# AD_DA.net
KiCad netlist of a schematic drawn in Altium Designer
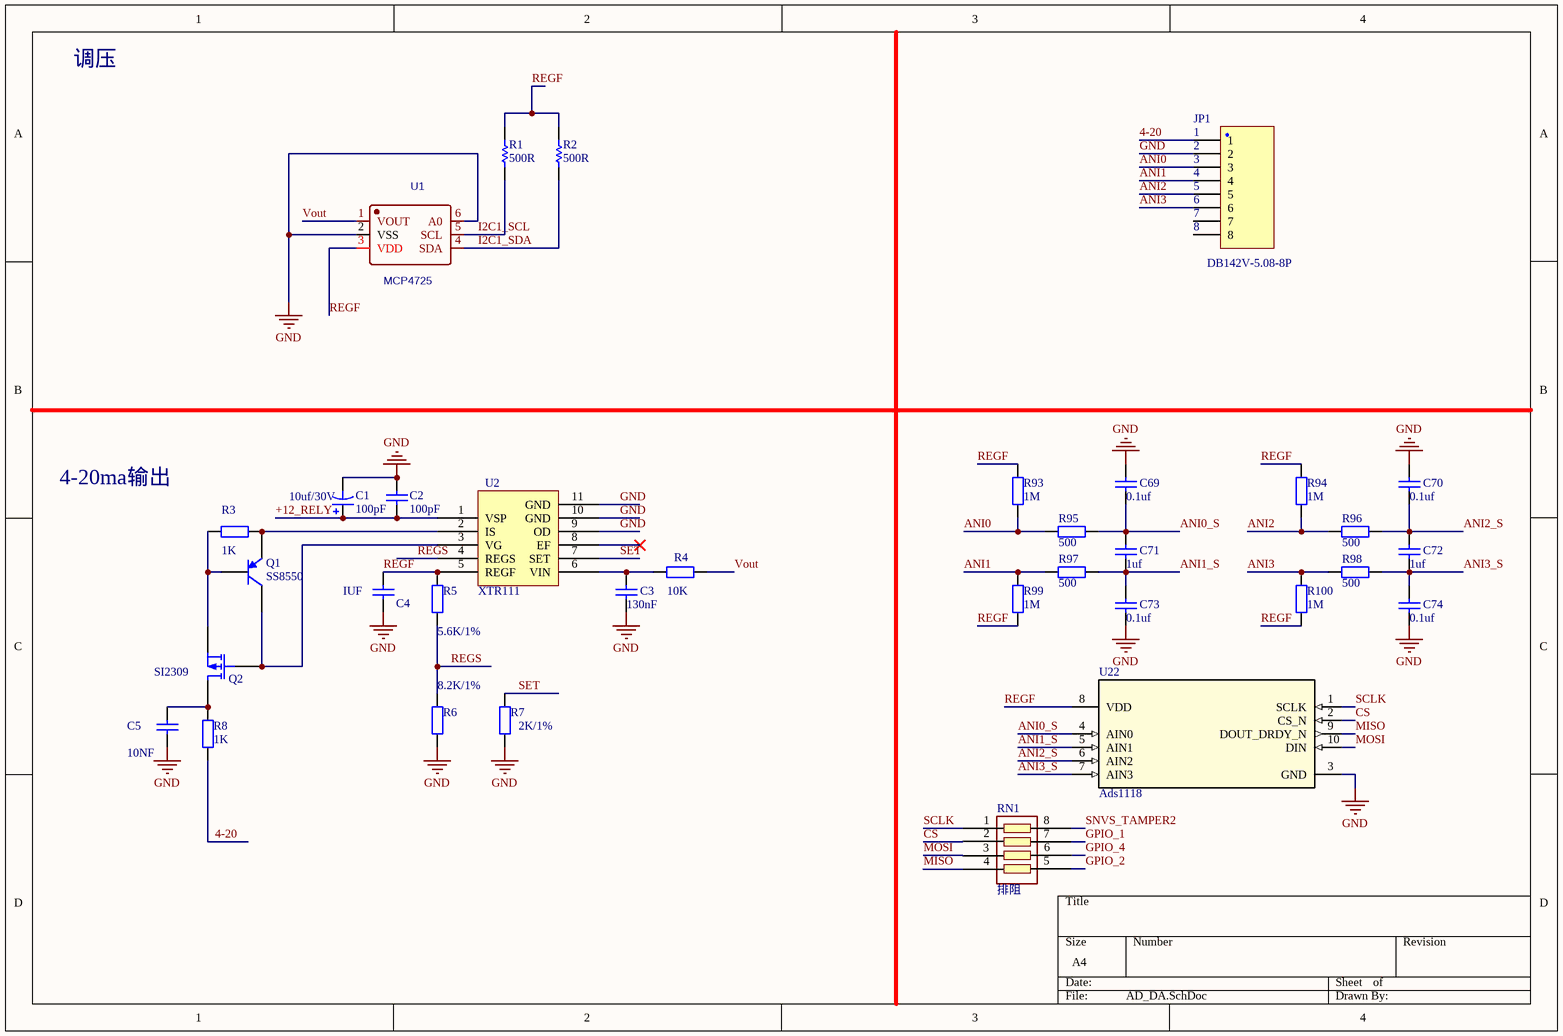
[diagram p0: AD_DA.SchDoc]

(export (version "E")
  (design (tool "Eeschema 10.0.6"))
  (components
    (comp (ref "C1")
      (value "10uf/30V")
      (footprint "CC5.05.4")
      (description "Polarized Capacitor (Radial)")
      (fields (field (name "ALTIUM_VALUE") "100pF") (field (name "PUBLISHER") "Altium Limited"))
      (libsource (lib "Miscellaneous Devices") (part "Cap Pol1"))
    )
    (comp (ref "C2")
      (value "100pF")
      (footprint "0603c")
      (description "Capacitor")
      (fields (field (name "Comment") "104") (field (name "PUBLISHER") "Altium Limited"))
      (libsource (lib "Miscellaneous Devices") (part "Cap"))
    )
    (comp (ref "C3")
      (value "130nF")
      (footprint "0603")
      (description "Capacitor")
      (libsource (lib "MyStandardSchLib") (part "Cap Smd"))
    )
    (comp (ref "C4")
      (value "IUF")
      (footprint "0603c")
      (description "Capacitor")
      (fields (field (name "PUBLISHER") "Altium Limited"))
      (libsource (lib "Miscellaneous Devices") (part "Cap"))
    )
    (comp (ref "C5")
      (value "10NF")
      (footprint "0603c")
      (description "Capacitor")
      (fields (field (name "PUBLISHER") "Altium Limited"))
      (libsource (lib "Miscellaneous Devices") (part "Cap"))
    )
    (comp (ref "C69")
      (value "0.1uf")
      (footprint "0603c")
      (description "Capacitor")
      (libsource (lib "MyStandardSchLib") (part "Cap Smd"))
    )
    (comp (ref "C70")
      (value "0.1uf")
      (footprint "0603c")
      (description "Capacitor")
      (libsource (lib "MyStandardSchLib") (part "Cap Smd"))
    )
    (comp (ref "C71")
      (value "1uf")
      (footprint "0603c")
      (description "Capacitor")
      (libsource (lib "MyStandardSchLib") (part "Cap Smd"))
    )
    (comp (ref "C72")
      (value "1uf")
      (footprint "0603c")
      (description "Capacitor")
      (libsource (lib "MyStandardSchLib") (part "Cap Smd"))
    )
    (comp (ref "C73")
      (value "0.1uf")
      (footprint "0603c")
      (description "Capacitor")
      (libsource (lib "MyStandardSchLib") (part "Cap Smd"))
    )
    (comp (ref "C74")
      (value "0.1uf")
      (footprint "0603c")
      (description "Capacitor")
      (libsource (lib "MyStandardSchLib") (part "Cap Smd"))
    )
    (comp (ref "JP1")
      (value "DB142V-5.08-8P")
      (footprint "DB142V-5.08-8P")
      (libsource (lib "Extra_Board_Mini") (part "DB142V-5.08-8P"))
    )
    (comp (ref "Q1")
      (value "SS8550")
      (footprint "SOT-23")
      (description "PNP Bipolar Transistor")
      (fields (field (name "PUBLISHER") "Altium Limited"))
      (libsource (lib "Miscellaneous Devices") (part "PNP"))
    )
    (comp (ref "Q2")
      (value "SI2309")
      (footprint "SOT-23")
      (description "P-Channel MOSFET")
      (fields (field (name "PUBLISHER") "Altium Limited"))
      (libsource (lib "Miscellaneous Devices") (part "MOSFET-P"))
    )
    (comp (ref "R1")
      (value "500R")
      (footprint "0603r")
      (description "Resistor")
      (fields (field (name "PUBLISHER") "Altium Limited"))
      (libsource (lib "WarShip_ExtraBoard") (part "RES"))
    )
    (comp (ref "R2")
      (value "500R")
      (footprint "0603r")
      (description "Resistor")
      (fields (field (name "PUBLISHER") "Altium Limited"))
      (libsource (lib "WarShip_ExtraBoard") (part "RES"))
    )
    (comp (ref "R3")
      (value "1K")
      (footprint "0603_R")
      (description "Resistor")
      (fields (field (name "Comment") "15R") (field (name "PUBLISHER") "Altium Limited"))
      (libsource (lib "") (part "Res2_2"))
    )
    (comp (ref "R4")
      (value "10K")
      (footprint "0603_R")
      (description "Resistor")
      (fields (field (name "PUBLISHER") "Altium Limited"))
      (libsource (lib "") (part "Res2_3"))
    )
    (comp (ref "R5")
      (value "5.6K/1%")
      (footprint "0603_R")
      (description "Resistor")
      (fields (field (name "PUBLISHER") "Altium Limited"))
      (libsource (lib "Miscellaneous Devices") (part "Res2"))
    )
    (comp (ref "R6")
      (value "8.2K/1%")
      (footprint "0603_R")
      (description "Resistor")
      (fields (field (name "PUBLISHER") "Altium Limited"))
      (libsource (lib "Miscellaneous Devices") (part "Res2"))
    )
    (comp (ref "R7")
      (value "2K/1%")
      (footprint "0603_R")
      (description "Resistor")
      (fields (field (name "PUBLISHER") "Altium Limited"))
      (libsource (lib "") (part "Res2_1"))
    )
    (comp (ref "R8")
      (value "1K")
      (footprint "0603_R")
      (description "Resistor")
      (fields (field (name "Comment") "15R") (field (name "PUBLISHER") "Altium Limited"))
      (libsource (lib "Miscellaneous Devices") (part "Res2"))
    )
    (comp (ref "R93")
      (value "1M")
      (footprint "0603r")
      (description "Resistor")
      (fields (field (name "PUBLISHER") "Altium Limited"))
      (libsource (lib "") (part "Res2_1"))
    )
    (comp (ref "R94")
      (value "1M")
      (footprint "0603r")
      (description "Resistor")
      (fields (field (name "PUBLISHER") "Altium Limited"))
      (libsource (lib "") (part "Res2_1"))
    )
    (comp (ref "R95")
      (value "500")
      (footprint "0603r")
      (description "Resistor")
      (fields (field (name "PUBLISHER") "Altium Limited"))
      (libsource (lib "") (part "Res2_2"))
    )
    (comp (ref "R96")
      (value "500")
      (footprint "0603r")
      (description "Resistor")
      (fields (field (name "PUBLISHER") "Altium Limited"))
      (libsource (lib "") (part "Res2_2"))
    )
    (comp (ref "R97")
      (value "500")
      (footprint "0603r")
      (description "Resistor")
      (fields (field (name "PUBLISHER") "Altium Limited"))
      (libsource (lib "") (part "Res2_3"))
    )
    (comp (ref "R98")
      (value "500")
      (footprint "0603r")
      (description "Resistor")
      (fields (field (name "PUBLISHER") "Altium Limited"))
      (libsource (lib "") (part "Res2_3"))
    )
    (comp (ref "R99")
      (value "1M")
      (footprint "0603r")
      (description "Resistor")
      (fields (field (name "PUBLISHER") "Altium Limited"))
      (libsource (lib "Miscellaneous Devices") (part "Res2"))
    )
    (comp (ref "R100")
      (value "1M")
      (footprint "0603r")
      (description "Resistor")
      (fields (field (name "PUBLISHER") "Altium Limited"))
      (libsource (lib "Miscellaneous Devices") (part "Res2"))
    )
    (comp (ref "RN1")
      (value "排阻")
      (footprint "RES_Network")
      (libsource (lib "Extra_Board_Mini") (part "Res_Network"))
    )
    (comp (ref "U1")
      (value "MCP4725")
      (footprint "MCP4725")
      (fields
        (field (name "BOM_MANUFACTURER PART") "MCP4725A0T-E/CH")
        (field (name "BOM_SUPPLIER PART") "C144198")
        (field (name "CONTRIBUTOR") "LCSC")
      )
      (libsource (lib "4_20MA_I2C") (part "MCP4725A0T-E/CH"))
    )
    (comp (ref "U2") (value "XTR111") (footprint "XTR111") (libsource (lib "XTR111") (part "XTR111")))
    (comp (ref "U22")
      (value "Ads1118")
      (footprint "ads1118")
      (libsource (lib "Extra_Board_Mini") (part "Ads1118"))
    )
  )
  (nets
    (net (code "1") (name "/+12_RELY") (class "Default")
      (node (ref "C1") (pin "1") (pinfunction "1_1") (pintype "passive"))
      (node (ref "C2") (pin "2") (pinfunction "2_2") (pintype "passive"))
      (node (ref "U2") (pin "1") (pinfunction "VSP_1") (pintype "passive"))
    )
    (net (code "2") (name "/4-20") (class "Default")
      (node (ref "JP1") (pin "1") (pinfunction "1_1") (pintype "passive"))
      (node (ref "R8") (pin "2") (pinfunction "2_2") (pintype "passive"))
    )
    (net (code "3") (name "/ANI0") (class "Default")
      (node (ref "JP1") (pin "3") (pinfunction "3_3") (pintype "passive"))
      (node (ref "R93") (pin "1") (pinfunction "1_1") (pintype "passive"))
      (node (ref "R95") (pin "2") (pinfunction "2_2") (pintype "passive"))
    )
    (net (code "4") (name "/ANI0_S") (class "Default")
      (node (ref "C69") (pin "2") (pinfunction "2_2") (pintype "passive"))
      (node (ref "C71") (pin "1") (pinfunction "1_1") (pintype "passive"))
      (node (ref "R95") (pin "1") (pinfunction "1_1") (pintype "passive"))
      (node (ref "U22") (pin "4") (pinfunction "AIN0_4") (pintype "input"))
    )
    (net (code "5") (name "/ANI1") (class "Default")
      (node (ref "JP1") (pin "4") (pinfunction "4_4") (pintype "passive"))
      (node (ref "R97") (pin "1") (pinfunction "1_1") (pintype "passive"))
      (node (ref "R99") (pin "1") (pinfunction "1_1") (pintype "passive"))
    )
    (net (code "6") (name "/ANI1_S") (class "Default")
      (node (ref "C71") (pin "2") (pinfunction "2_2") (pintype "passive"))
      (node (ref "C73") (pin "1") (pinfunction "1_1") (pintype "passive"))
      (node (ref "R97") (pin "2") (pinfunction "2_2") (pintype "passive"))
      (node (ref "U22") (pin "5") (pinfunction "AIN1_5") (pintype "input"))
    )
    (net (code "7") (name "/ANI2") (class "Default")
      (node (ref "JP1") (pin "5") (pinfunction "5_5") (pintype "passive"))
      (node (ref "R94") (pin "1") (pinfunction "1_1") (pintype "passive"))
      (node (ref "R96") (pin "2") (pinfunction "2_2") (pintype "passive"))
    )
    (net (code "8") (name "/ANI2_S") (class "Default")
      (node (ref "C70") (pin "2") (pinfunction "2_2") (pintype "passive"))
      (node (ref "C72") (pin "1") (pinfunction "1_1") (pintype "passive"))
      (node (ref "R96") (pin "1") (pinfunction "1_1") (pintype "passive"))
      (node (ref "U22") (pin "6") (pinfunction "AIN2_6") (pintype "input"))
    )
    (net (code "9") (name "/ANI3") (class "Default")
      (node (ref "JP1") (pin "6") (pinfunction "6_6") (pintype "passive"))
      (node (ref "R100") (pin "1") (pinfunction "1_1") (pintype "passive"))
      (node (ref "R98") (pin "1") (pinfunction "1_1") (pintype "passive"))
    )
    (net (code "10") (name "/ANI3_S") (class "Default")
      (node (ref "C72") (pin "2") (pinfunction "2_2") (pintype "passive"))
      (node (ref "C74") (pin "1") (pinfunction "1_1") (pintype "passive"))
      (node (ref "R98") (pin "2") (pinfunction "2_2") (pintype "passive"))
      (node (ref "U22") (pin "7") (pinfunction "AIN3_7") (pintype "input"))
    )
    (net (code "11") (name "/CS") (class "Default")
      (node (ref "RN1") (pin "2") (pinfunction "2_2") (pintype "passive"))
      (node (ref "U22") (pin "2") (pinfunction "CS_N_2") (pintype "input"))
    )
    (net (code "12") (name "/GPIO_1") (class "Default")
      (node (ref "RN1") (pin "7") (pinfunction "7_7") (pintype "passive"))
    )
    (net (code "13") (name "/GPIO_2") (class "Default")
      (node (ref "RN1") (pin "5") (pinfunction "5_5") (pintype "passive"))
    )
    (net (code "14") (name "/GPIO_4") (class "Default")
      (node (ref "RN1") (pin "6") (pinfunction "6_6") (pintype "passive"))
    )
    (net (code "15") (name "/I2C1_SCL") (class "Default")
      (node (ref "R1") (pin "1") (pinfunction "1_1") (pintype "passive"))
      (node (ref "U1") (pin "5") (pinfunction "SCL_5") (pintype "passive"))
    )
    (net (code "16") (name "/I2C1_SDA") (class "Default")
      (node (ref "R2") (pin "1") (pinfunction "1_1") (pintype "passive"))
      (node (ref "U1") (pin "4") (pinfunction "SDA_4") (pintype "passive"))
    )
    (net (code "17") (name "/MISO") (class "Default")
      (node (ref "RN1") (pin "4") (pinfunction "4_4") (pintype "passive"))
      (node (ref "U22") (pin "9") (pinfunction "DOUT_DRDY_N_9") (pintype "output"))
    )
    (net (code "18") (name "/MOSI") (class "Default")
      (node (ref "RN1") (pin "3") (pinfunction "3_3") (pintype "passive"))
      (node (ref "U22") (pin "10") (pinfunction "DIN_10") (pintype "input"))
    )
    (net (code "19") (name "/REGF") (class "Default")
      (node (ref "C4") (pin "2") (pinfunction "2_2") (pintype "passive"))
      (node (ref "R1") (pin "2") (pinfunction "2_2") (pintype "passive"))
      (node (ref "R100") (pin "2") (pinfunction "2_2") (pintype "passive"))
      (node (ref "R2") (pin "2") (pinfunction "2_2") (pintype "passive"))
      (node (ref "R5") (pin "1") (pinfunction "1_1") (pintype "passive"))
      (node (ref "R93") (pin "2") (pinfunction "2_2") (pintype "passive"))
      (node (ref "R94") (pin "2") (pinfunction "2_2") (pintype "passive"))
      (node (ref "R99") (pin "2") (pinfunction "2_2") (pintype "passive"))
      (node (ref "U1") (pin "3") (pinfunction "VDD_3") (pintype "passive"))
      (node (ref "U2") (pin "5") (pinfunction "REGF_5") (pintype "passive"))
      (node (ref "U22") (pin "8") (pinfunction "VDD_8") (pintype "power_in"))
    )
    (net (code "20") (name "/REGS") (class "Default")
      (node (ref "R5") (pin "2") (pinfunction "2_2") (pintype "passive"))
      (node (ref "R6") (pin "1") (pinfunction "1_1") (pintype "passive"))
      (node (ref "U2") (pin "4") (pinfunction "REGS_4") (pintype "passive"))
    )
    (net (code "21") (name "/SCLK") (class "Default")
      (node (ref "RN1") (pin "1") (pinfunction "1_1") (pintype "passive"))
      (node (ref "U22") (pin "1") (pinfunction "SCLK_1") (pintype "input"))
    )
    (net (code "22") (name "/SET") (class "Default")
      (node (ref "R7") (pin "2") (pinfunction "2_2") (pintype "passive"))
      (node (ref "U2") (pin "7") (pinfunction "SET_7") (pintype "passive"))
    )
    (net (code "23") (name "/SNVS_TAMPER2") (class "Default")
      (node (ref "RN1") (pin "8") (pinfunction "8_8") (pintype "passive"))
    )
    (net (code "24") (name "/Vout") (class "Default")
      (node (ref "R4") (pin "2") (pinfunction "2_2") (pintype "passive"))
      (node (ref "U1") (pin "1") (pinfunction "VOUT_1") (pintype "passive"))
    )
    (net (code "25") (name "GND") (class "Default")
      (node (ref "C1") (pin "2") (pinfunction "2_2") (pintype "passive"))
      (node (ref "C2") (pin "1") (pinfunction "1_1") (pintype "passive"))
      (node (ref "C3") (pin "2") (pinfunction "2_2") (pintype "passive"))
      (node (ref "C4") (pin "1") (pinfunction "1_1") (pintype "passive"))
      (node (ref "C5") (pin "2") (pinfunction "2_2") (pintype "passive"))
      (node (ref "C69") (pin "1") (pinfunction "1_1") (pintype "passive"))
      (node (ref "C70") (pin "1") (pinfunction "1_1") (pintype "passive"))
      (node (ref "C73") (pin "2") (pinfunction "2_2") (pintype "passive"))
      (node (ref "C74") (pin "2") (pinfunction "2_2") (pintype "passive"))
      (node (ref "JP1") (pin "2") (pinfunction "2_2") (pintype "passive"))
      (node (ref "R6") (pin "2") (pinfunction "2_2") (pintype "passive"))
      (node (ref "R7") (pin "1") (pinfunction "1_1") (pintype "passive"))
      (node (ref "U1") (pin "2") (pinfunction "VSS_2") (pintype "passive"))
      (node (ref "U1") (pin "6") (pinfunction "A0_6") (pintype "passive"))
      (node (ref "U2") (pin "10") (pinfunction "GND_10") (pintype "passive"))
      (node (ref "U2") (pin "11") (pinfunction "GND_11") (pintype "passive"))
      (node (ref "U2") (pin "9") (pinfunction "OD_9") (pintype "passive"))
      (node (ref "U22") (pin "3") (pinfunction "GND_3") (pintype "power_in"))
    )
    (net (code "26") (name "Net-(Q1-B)") (class "Default")
      (node (ref "Q1") (pin "2") (pinfunction "B_2") (pintype "passive"))
      (node (ref "Q2") (pin "3") (pinfunction "S_3") (pintype "passive"))
      (node (ref "R3") (pin "2") (pinfunction "2_2") (pintype "passive"))
    )
    (net (code "27") (name "Net-(Q1-C)") (class "Default")
      (node (ref "Q1") (pin "1") (pinfunction "C_1") (pintype "passive"))
      (node (ref "Q2") (pin "2") (pinfunction "G_2") (pintype "passive"))
      (node (ref "U2") (pin "3") (pinfunction "VG_3") (pintype "passive"))
    )
    (net (code "28") (name "Net-(Q1-E)") (class "Default")
      (node (ref "Q1") (pin "3") (pinfunction "E_3") (pintype "passive"))
      (node (ref "R3") (pin "1") (pinfunction "1_1") (pintype "passive"))
      (node (ref "U2") (pin "2") (pinfunction "IS_2") (pintype "passive"))
    )
    (net (code "29") (name "Net-(Q2-D)") (class "Default")
      (node (ref "C5") (pin "1") (pinfunction "1_1") (pintype "passive"))
      (node (ref "Q2") (pin "1") (pinfunction "D_1") (pintype "passive"))
      (node (ref "R8") (pin "1") (pinfunction "1_1") (pintype "passive"))
    )
    (net (code "30") (name "Net-(U2-VIN)") (class "Default")
      (node (ref "C3") (pin "1") (pinfunction "1_1") (pintype "passive"))
      (node (ref "R4") (pin "1") (pinfunction "1_1") (pintype "passive"))
      (node (ref "U2") (pin "6") (pinfunction "VIN_6") (pintype "passive"))
    )
    (net (code "31") (name "unconnected-(JP1-Pad7)") (class "Default")
      (node (ref "JP1") (pin "7") (pinfunction "7_7") (pintype "passive"))
    )
    (net (code "32") (name "unconnected-(JP1-Pad8)") (class "Default")
      (node (ref "JP1") (pin "8") (pinfunction "8_8") (pintype "passive"))
    )
    (net (code "33") (name "unconnected-(U2-EF-Pad8)") (class "Default")
      (node (ref "U2") (pin "8") (pinfunction "EF_8") (pintype "passive+no_connect"))
    )
  )
)
